# CanTransceiver.net
KiCad netlist of a schematic drawn in Altium Designer
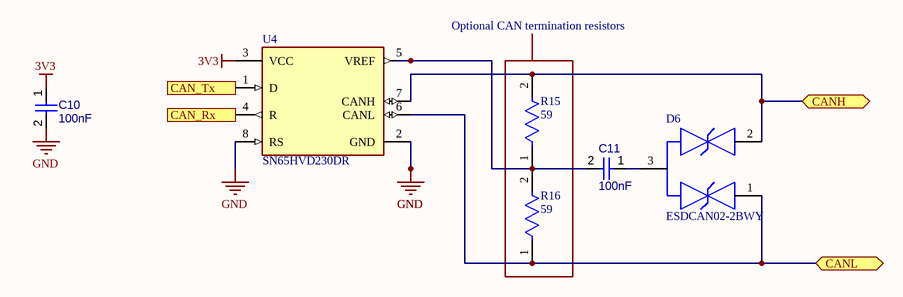
[diagram p0: CanTransceiver.SchDoc]

(export (version "E")
  (design (tool "Eeschema 10.0.6"))
  (components
    (comp (ref "C10")
      (value "100nF")
      (footprint "CAPC0402(1005)60_L")
      (description "Chip Capacitor, 100nF +/-20%, 10V, 0402, Thickness 0.6 mm")
      (fields (field (name "TOLERANCE") "20%"))
      (libsource (lib "Bronco Racing") (part "CAP-NP-2"))
    )
    (comp (ref "C11")
      (value "100nF")
      (footprint "CAPC0402(1005)60_L")
      (description "Chip Capacitor, 100nF +/-20%, 10V, 0402, Thickness 0.6 mm")
      (fields (field (name "TOLERANCE") "20%"))
      (libsource (lib "Bronco Racing") (part "CAP-NP-2"))
    )
    (comp (ref "D6")
      (value "ESDCAN02-2BWY")
      (footprint "FP-SOT323-3L-MFG")
      (description "TVS DIODE 26.5V 44V SOT323-3")
      (fields
        (field (name "MANUFACTURER") "STMicroelectronics")
        (field (name "OCTOPART") "https://octopart.com/esdcan02-2bwy-stmicroelectronics-58631133")
      )
      (libsource (lib "Altium Content Vault") (part "0b9019fb5e52ed66df21ec1535be59d"))
    )
    (comp (ref "R15")
      (value "59")
      (footprint "FP-CRCW0805-e3-IPC_B")
      (description "RES Thick Film, 59Ω, 1%, 0.125W, 100ppm/°C, 0805")
      (fields (field (name "TOLERANCE") "1%"))
      (libsource (lib "Altium Content Vault") (part "1029c3af85768c4190bb7ad29bc67b5"))
    )
    (comp (ref "R16")
      (value "59")
      (footprint "FP-CRCW0805-e3-IPC_B")
      (description "RES Thick Film, 59Ω, 1%, 0.125W, 100ppm/°C, 0805")
      (fields (field (name "TOLERANCE") "1%"))
      (libsource (lib "Altium Content Vault") (part "1029c3af85768c4190bb7ad29bc67b5"))
    )
    (comp (ref "U4")
      (value "SN65HVD230DR")
      (footprint "FP-D0008A-IPC_A")
      (description "IC TRANSCEIVER HALF 1/1 8SOIC")
      (libsource (lib "Altium Content Vault") (part "43b56812b1adf0e60a7acfb7c27ab91"))
    )
  )
  (nets
    (net (code "1") (name "/CANH") (class "Default")
      (node (ref "D6") (pin "2") (pinfunction "2_2") (pintype "passive"))
      (node (ref "R15") (pin "2") (pinfunction "2_2") (pintype "passive"))
      (node (ref "U4") (pin "7") (pinfunction "CANH_7") (pintype "bidirectional"))
    )
    (net (code "2") (name "/CANL") (class "Default")
      (node (ref "D6") (pin "1") (pinfunction "1_1") (pintype "passive"))
      (node (ref "R16") (pin "1") (pinfunction "1_1") (pintype "passive"))
      (node (ref "U4") (pin "6") (pinfunction "CANL_6") (pintype "bidirectional"))
    )
    (net (code "3") (name "/CAN_Rx") (class "Default")
      (node (ref "U4") (pin "4") (pinfunction "R_4") (pintype "output"))
    )
    (net (code "4") (name "/CAN_Tx") (class "Default")
      (node (ref "U4") (pin "1") (pinfunction "D_1") (pintype "input"))
    )
    (net (code "5") (name "3V3") (class "Default")
      (node (ref "C10") (pin "1") (pinfunction "1_1") (pintype "passive"))
      (node (ref "U4") (pin "3") (pinfunction "VCC_3") (pintype "power_in"))
    )
    (net (code "6") (name "GND") (class "Default")
      (node (ref "C10") (pin "2") (pinfunction "2_2") (pintype "passive"))
      (node (ref "U4") (pin "2") (pinfunction "GND_2") (pintype "power_in"))
      (node (ref "U4") (pin "8") (pinfunction "RS_8") (pintype "input"))
    )
    (net (code "7") (name "Net-(C11-Pad1)") (class "Default")
      (node (ref "C11") (pin "1") (pinfunction "1_1") (pintype "passive"))
      (node (ref "D6") (pin "3") (pinfunction "3_3") (pintype "passive"))
    )
    (net (code "8") (name "Net-(U4-VREF)") (class "Default")
      (node (ref "C11") (pin "2") (pinfunction "2_2") (pintype "passive"))
      (node (ref "R15") (pin "1") (pinfunction "1_1") (pintype "passive"))
      (node (ref "R16") (pin "2") (pinfunction "2_2") (pintype "passive"))
      (node (ref "U4") (pin "5") (pinfunction "VREF_5") (pintype "output"))
    )
  )
)
